# Thermistor_Linearization.net
KiCad netlist of a schematic drawn in Altium Designer
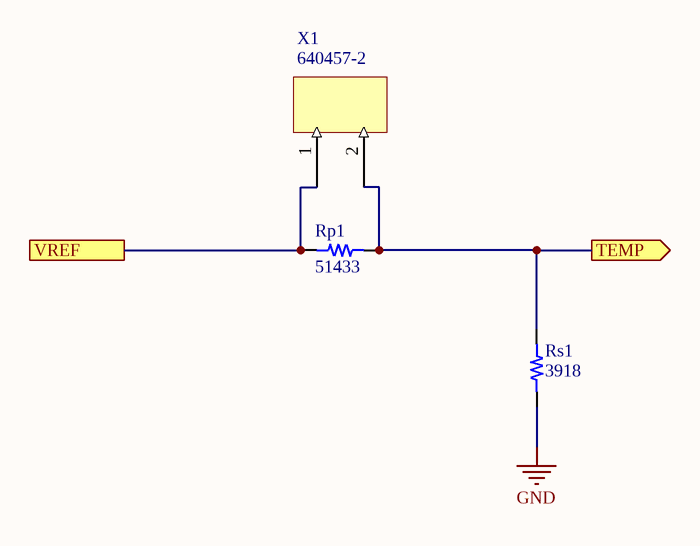
[diagram p0: Thermistor Linearization.SchDoc]

(export (version "E")
  (design (tool "Eeschema 10.0.6"))
  (components
    (comp (ref "Rp1")
      (value "51433")
      (footprint "RES 0603/1608")
      (fields (field (name "RESISTANCE") "51433"))
      (libsource (lib "altlib") (part "Resistor"))
    )
    (comp (ref "Rs1")
      (value "3918")
      (footprint "RES 0603/1608")
      (fields (field (name "RESISTANCE") "3918"))
      (libsource (lib "altlib") (part "Resistor"))
    )
    (comp (ref "X1")
      (value "640457-2")
      (footprint "640457-2:640457")
      (description "2 pin header")
      (fields (field (name "CREATEDBY") "Jason"))
      (libsource (lib "altlib") (part "640457-2"))
    )
  )
  (nets
    (net (code "1") (name "/TEMP") (class "Default")
      (node (ref "Rp1") (pin "2") (pinfunction "2_2") (pintype "passive"))
      (node (ref "Rs1") (pin "2") (pinfunction "2_2") (pintype "passive"))
      (node (ref "X1") (pin "2") (pintype "input"))
    )
    (net (code "2") (name "/VREF") (class "Default")
      (node (ref "Rp1") (pin "1") (pinfunction "1_1") (pintype "passive"))
      (node (ref "X1") (pin "1") (pintype "input"))
    )
    (net (code "3") (name "GND") (class "Default")
      (node (ref "Rs1") (pin "1") (pinfunction "1_1") (pintype "passive"))
    )
  )
)
